# LT8311-Main.net
KiCad netlist of a schematic drawn in Altium Designer
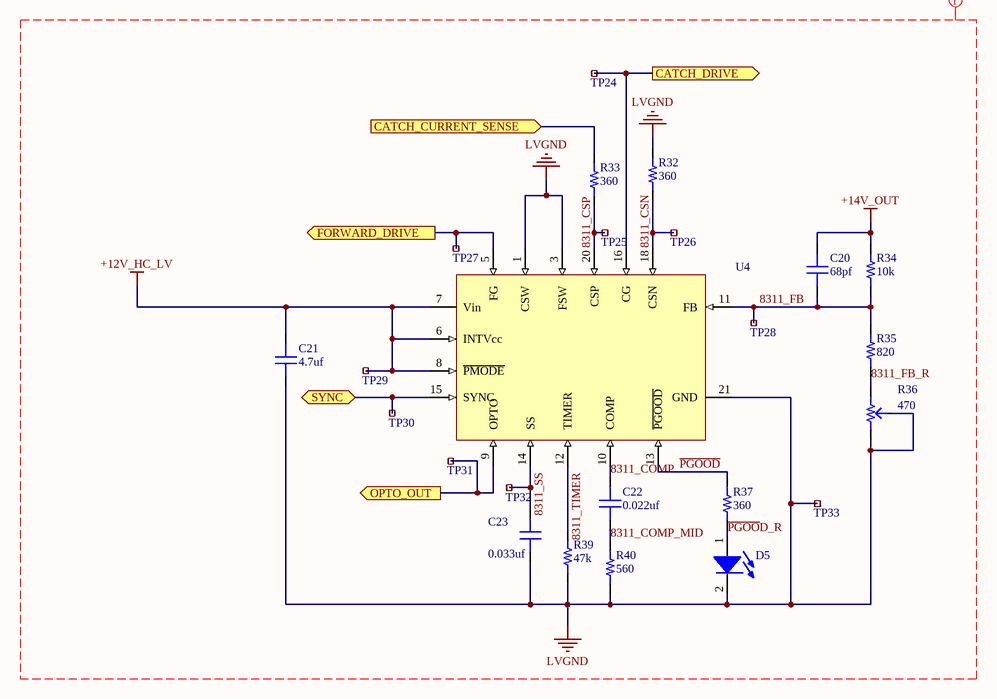
[diagram p0: LT8311-Main.SchDoc]

(export (version "E")
  (design (tool "Eeschema 10.0.6"))
  (components
    (comp (ref "C20")
      (value "68pf")
      (footprint "CAP 0603/1608")
      (fields
        (field (name "Comment") "Capacitor MLCC 68pf 25V CAP 0603/1608")
        (field (name "CREATED_BY") "Nick Mah")
      )
      (libsource (lib "Altium-Lib") (part "Capacitor"))
    )
    (comp (ref "C21")
      (value "4.7uf")
      (footprint "CAP 0805/2012")
      (fields
        (field (name "Comment") "Capacitor MLCC 4.7uf 25V CAP 0805/2012")
        (field (name "CREATED_BY") "Nick Mah")
      )
      (libsource (lib "Altium-Lib") (part "Capacitor"))
    )
    (comp (ref "C22")
      (value "0.022uf")
      (footprint "CAP 0603/1608")
      (fields
        (field (name "Comment") "Capacitor MLCC 0.022uf 16V CAP 0603/1608")
        (field (name "CREATED_BY") "Nick Mah")
      )
      (libsource (lib "Altium-Lib") (part "Capacitor"))
    )
    (comp (ref "C23")
      (value "0.033uf")
      (footprint "CAP 0603/1608")
      (fields
        (field (name "Comment") "Capacitor MLCC 0.033uf 16V CAP 0603/1608")
        (field (name "CREATED_BY") "Nick Mah")
      )
      (libsource (lib "Altium-Lib") (part "Capacitor"))
    )
    (comp (ref "D5") (value "~") (footprint "0805_LED") (libsource (lib "Altium-Lib") (part "LED")))
    (comp (ref "R32")
      (value "360")
      (footprint "RES 0603/1608")
      (fields
        (field (name "TOLERANCE") "1%")
        (field (name "POWER") "1/10W")
        (field (name "Comment") "Resistor 360 0603 1/10W 1%")
        (field (name "CREATED_BY") "Nick Mah")
      )
      (libsource (lib "Altium-Lib") (part "Resistor"))
    )
    (comp (ref "R33")
      (value "360")
      (footprint "RES 0603/1608")
      (fields
        (field (name "TOLERANCE") "1%")
        (field (name "POWER") "1/10W")
        (field (name "Comment") "Resistor 360 0603 1/10W 1%")
        (field (name "CREATED_BY") "Nick Mah")
      )
      (libsource (lib "Altium-Lib") (part "Resistor"))
    )
    (comp (ref "R34")
      (value "10k")
      (footprint "RES 0603/1608")
      (fields
        (field (name "TOLERANCE") "1%")
        (field (name "POWER") "1/10W")
        (field (name "Comment") "Resistor 10k 0603 1/10W 1%")
        (field (name "CREATED_BY") "Nick Mah")
      )
      (libsource (lib "Altium-Lib") (part "Resistor"))
    )
    (comp (ref "R35")
      (value "820")
      (footprint "RES 0603/1608")
      (fields
        (field (name "TOLERANCE") "1%")
        (field (name "POWER") "1/10W")
        (field (name "Comment") "Resistor 820 0603 1/10W 1%")
        (field (name "CREATED_BY") "Nick Mah")
      )
      (libsource (lib "Altium-Lib") (part "Resistor"))
    )
    (comp (ref "R36")
      (value "470")
      (footprint "PT6WV")
      (description "470 Ohm 1 Gang Linear Through Hole Potentiometer None 1 Turn Carbon 0.1W, 1/10W PC Pins")
      (fields
        (field (name "TOLERANCE") "20%")
        (field (name "POWER") "1/10W")
        (field (name "CREATED_BY") "Nick Mah")
      )
      (libsource (lib "Altium-Lib") (part "Pot"))
    )
    (comp (ref "R37")
      (value "360")
      (footprint "RES 0603/1608")
      (fields
        (field (name "TOLERANCE") "1%")
        (field (name "POWER") "1/10W")
        (field (name "Comment") "Resistor 360 0603 1/10W 1%")
        (field (name "CREATED_BY") "Nick Mah")
      )
      (libsource (lib "Altium-Lib") (part "Resistor"))
    )
    (comp (ref "R39")
      (value "47k")
      (footprint "RES 0603/1608")
      (fields
        (field (name "TOLERANCE") "1%")
        (field (name "POWER") "1/10W")
        (field (name "Comment") "Resistor 47k 0603 1/10W 1%")
        (field (name "CREATED_BY") "Nick Mah")
      )
      (libsource (lib "Altium-Lib") (part "Resistor"))
    )
    (comp (ref "R40")
      (value "560")
      (footprint "RES 0603/1608")
      (fields
        (field (name "TOLERANCE") "1%")
        (field (name "POWER") "1/10W")
        (field (name "Comment") "Resistor 560 0603 1/10W 1%")
        (field (name "CREATED_BY") "Nick Mah")
      )
      (libsource (lib "Altium-Lib") (part "Resistor"))
    )
    (comp (ref "TP24")
      (value "RCU-0C")
      (footprint "5029")
      (description "Test point")
      (fields
        (field (name "MFRPARTNO") "5029")
        (field (name "COMPONENTLINK1URL") "file:///C:/Users/Jason%20Zhou/Downloads/5029.PDF")
        (field (name "CREATED_BY") "Jason Zhou")
      )
      (libsource (lib "Altium-Lib") (part "RCU-0C"))
    )
    (comp (ref "TP25")
      (value "RCU-0C")
      (footprint "5029")
      (description "Test point")
      (fields
        (field (name "MFRPARTNO") "5029")
        (field (name "COMPONENTLINK1URL") "file:///C:/Users/Jason%20Zhou/Downloads/5029.PDF")
        (field (name "CREATED_BY") "Jason Zhou")
      )
      (libsource (lib "Altium-Lib") (part "RCU-0C"))
    )
    (comp (ref "TP26")
      (value "RCU-0C")
      (footprint "5029")
      (description "Test point")
      (fields
        (field (name "MFRPARTNO") "5029")
        (field (name "COMPONENTLINK1URL") "file:///C:/Users/Jason%20Zhou/Downloads/5029.PDF")
        (field (name "CREATED_BY") "Jason Zhou")
      )
      (libsource (lib "Altium-Lib") (part "RCU-0C"))
    )
    (comp (ref "TP27")
      (value "RCU-0C")
      (footprint "5029")
      (description "Test point")
      (fields
        (field (name "MFRPARTNO") "5029")
        (field (name "COMPONENTLINK1URL") "file:///C:/Users/Jason%20Zhou/Downloads/5029.PDF")
        (field (name "CREATED_BY") "Jason Zhou")
      )
      (libsource (lib "Altium-Lib") (part "RCU-0C"))
    )
    (comp (ref "TP28")
      (value "RCU-0C")
      (footprint "5029")
      (description "Test point")
      (fields
        (field (name "MFRPARTNO") "5029")
        (field (name "COMPONENTLINK1URL") "file:///C:/Users/Jason%20Zhou/Downloads/5029.PDF")
        (field (name "CREATED_BY") "Jason Zhou")
      )
      (libsource (lib "Altium-Lib") (part "RCU-0C"))
    )
    (comp (ref "TP29")
      (value "RCU-0C")
      (footprint "5029")
      (description "Test point")
      (fields
        (field (name "MFRPARTNO") "5029")
        (field (name "COMPONENTLINK1URL") "file:///C:/Users/Jason%20Zhou/Downloads/5029.PDF")
        (field (name "CREATED_BY") "Jason Zhou")
      )
      (libsource (lib "Altium-Lib") (part "RCU-0C"))
    )
    (comp (ref "TP30")
      (value "RCU-0C")
      (footprint "5029")
      (description "Test point")
      (fields
        (field (name "MFRPARTNO") "5029")
        (field (name "COMPONENTLINK1URL") "file:///C:/Users/Jason%20Zhou/Downloads/5029.PDF")
        (field (name "CREATED_BY") "Jason Zhou")
      )
      (libsource (lib "Altium-Lib") (part "RCU-0C"))
    )
    (comp (ref "TP31")
      (value "RCU-0C")
      (footprint "5029")
      (description "Test point")
      (fields
        (field (name "MFRPARTNO") "5029")
        (field (name "COMPONENTLINK1URL") "file:///C:/Users/Jason%20Zhou/Downloads/5029.PDF")
        (field (name "CREATED_BY") "Jason Zhou")
      )
      (libsource (lib "Altium-Lib") (part "RCU-0C"))
    )
    (comp (ref "TP32")
      (value "RCU-0C")
      (footprint "5029")
      (description "Test point")
      (fields
        (field (name "MFRPARTNO") "5029")
        (field (name "COMPONENTLINK1URL") "file:///C:/Users/Jason%20Zhou/Downloads/5029.PDF")
        (field (name "CREATED_BY") "Jason Zhou")
      )
      (libsource (lib "Altium-Lib") (part "RCU-0C"))
    )
    (comp (ref "TP33")
      (value "RCU-0C")
      (footprint "5029")
      (description "Test point")
      (fields
        (field (name "MFRPARTNO") "5029")
        (field (name "COMPONENTLINK1URL") "file:///C:/Users/Jason%20Zhou/Downloads/5029.PDF")
        (field (name "CREATED_BY") "Jason Zhou")
      )
      (libsource (lib "Altium-Lib") (part "RCU-0C"))
    )
    (comp (ref "U4")
      (value "~")
      (footprint "FE20(16)")
      (description "Power Supply Controller Secondary-Side Controller")
      (fields (field (name "MFRPARTNO") "LT8311FE") (field (name "CREATED_BY") "Jason"))
      (libsource (lib "Altium-Lib") (part "LT8311"))
    )
  )
  (nets
    (net (code "1") (name "+12V_HC_LV") (class "Default")
      (node (ref "C21") (pin "2") (pinfunction "2_2") (pintype "passive"))
      (node (ref "TP29") (pin "1") (pintype "passive"))
      (node (ref "U4") (pin "6") (pinfunction "INTVcc_6") (pintype "input"))
      (node (ref "U4") (pin "7") (pinfunction "Vin_7") (pintype "power_in"))
      (node (ref "U4") (pin "8") (pinfunction "~{PMODE}_8") (pintype "input"))
    )
    (net (code "2") (name "+14V_OUT") (class "Default")
      (node (ref "C20") (pin "2") (pinfunction "2_2") (pintype "passive"))
      (node (ref "R34") (pin "2") (pinfunction "2_2") (pintype "passive"))
    )
    (net (code "3") (name "/8311_COMP") (class "Default")
      (node (ref "C22") (pin "2") (pinfunction "2_2") (pintype "passive"))
      (node (ref "U4") (pin "10") (pinfunction "COMP_10") (pintype "input"))
    )
    (net (code "4") (name "/8311_COMP_MID") (class "Default")
      (node (ref "C22") (pin "1") (pinfunction "1_1") (pintype "passive"))
      (node (ref "R40") (pin "2") (pinfunction "2_2") (pintype "passive"))
    )
    (net (code "5") (name "/8311_CSN") (class "Default")
      (node (ref "R32") (pin "1") (pinfunction "1_1") (pintype "passive"))
      (node (ref "TP26") (pin "1") (pintype "passive"))
      (node (ref "U4") (pin "18") (pinfunction "CSN_18") (pintype "input"))
    )
    (net (code "6") (name "/8311_CSP") (class "Default")
      (node (ref "R33") (pin "1") (pinfunction "1_1") (pintype "passive"))
      (node (ref "TP25") (pin "1") (pintype "passive"))
      (node (ref "U4") (pin "20") (pinfunction "CSP_20") (pintype "input"))
    )
    (net (code "7") (name "/8311_FB") (class "Default")
      (node (ref "C20") (pin "1") (pinfunction "1_1") (pintype "passive"))
      (node (ref "R34") (pin "1") (pinfunction "1_1") (pintype "passive"))
      (node (ref "R35") (pin "2") (pinfunction "2_2") (pintype "passive"))
      (node (ref "TP28") (pin "1") (pintype "passive"))
      (node (ref "U4") (pin "11") (pinfunction "FB_11") (pintype "input"))
    )
    (net (code "8") (name "/8311_FB_R") (class "Default")
      (node (ref "R35") (pin "1") (pinfunction "1_1") (pintype "passive"))
      (node (ref "R36") (pin "1") (pinfunction "1_1") (pintype "passive"))
    )
    (net (code "9") (name "/8311_SS") (class "Default")
      (node (ref "C23") (pin "1") (pinfunction "1_1") (pintype "passive"))
      (node (ref "TP32") (pin "1") (pintype "passive"))
      (node (ref "U4") (pin "14") (pinfunction "SS_14") (pintype "input"))
    )
    (net (code "10") (name "/8311_TIMER") (class "Default")
      (node (ref "R39") (pin "2") (pinfunction "2_2") (pintype "passive"))
      (node (ref "U4") (pin "12") (pinfunction "TIMER_12") (pintype "input"))
    )
    (net (code "11") (name "/CATCH_CURRENT_SENSE") (class "Default")
      (node (ref "R33") (pin "2") (pinfunction "2_2") (pintype "passive"))
    )
    (net (code "12") (name "/CATCH_DRIVE") (class "Default")
      (node (ref "TP24") (pin "1") (pintype "passive"))
      (node (ref "U4") (pin "16") (pinfunction "CG_16") (pintype "input"))
    )
    (net (code "13") (name "/FORWARD_DRIVE") (class "Default")
      (node (ref "TP27") (pin "1") (pintype "passive"))
      (node (ref "U4") (pin "5") (pinfunction "FG_5") (pintype "input"))
    )
    (net (code "14") (name "/OPTO_OUT") (class "Default")
      (node (ref "TP31") (pin "1") (pintype "passive"))
      (node (ref "U4") (pin "9") (pinfunction "OPTO_9") (pintype "input"))
    )
    (net (code "15") (name "/SYNC") (class "Default")
      (node (ref "TP30") (pin "1") (pintype "passive"))
      (node (ref "U4") (pin "15") (pinfunction "SYNC_15") (pintype "input"))
    )
    (net (code "16") (name "/~{PGOOD}") (class "Default")
      (node (ref "R37") (pin "2") (pinfunction "2_2") (pintype "passive"))
      (node (ref "U4") (pin "13") (pinfunction "~{PGOOD}_13") (pintype "input"))
    )
    (net (code "17") (name "/~{PGOO}D_R") (class "Default")
      (node (ref "D5") (pin "1") (pinfunction "A_1") (pintype "passive"))
      (node (ref "R37") (pin "1") (pinfunction "1_1") (pintype "passive"))
    )
    (net (code "18") (name "LVGND") (class "Default")
      (node (ref "C21") (pin "1") (pinfunction "1_1") (pintype "passive"))
      (node (ref "C23") (pin "2") (pinfunction "2_2") (pintype "passive"))
      (node (ref "D5") (pin "2") (pinfunction "K_2") (pintype "passive"))
      (node (ref "R32") (pin "2") (pinfunction "2_2") (pintype "passive"))
      (node (ref "R36") (pin "2") (pinfunction "2_2") (pintype "passive"))
      (node (ref "R39") (pin "1") (pinfunction "1_1") (pintype "passive"))
      (node (ref "R40") (pin "1") (pinfunction "1_1") (pintype "passive"))
      (node (ref "TP33") (pin "1") (pintype "passive"))
      (node (ref "U4") (pin "1") (pinfunction "CSW_1") (pintype "input"))
      (node (ref "U4") (pin "21") (pinfunction "GND_21") (pintype "power_in"))
      (node (ref "U4") (pin "3") (pinfunction "FSW_3") (pintype "input"))
    )
    (net (code "19") (name "unconnected-(R36-Pad3)") (class "Default")
      (node (ref "R36") (pin "3") (pinfunction "3_3") (pintype "passive"))
    )
  )
)
